# BoostSupply.net
KiCad netlist of a schematic drawn in Altium Designer
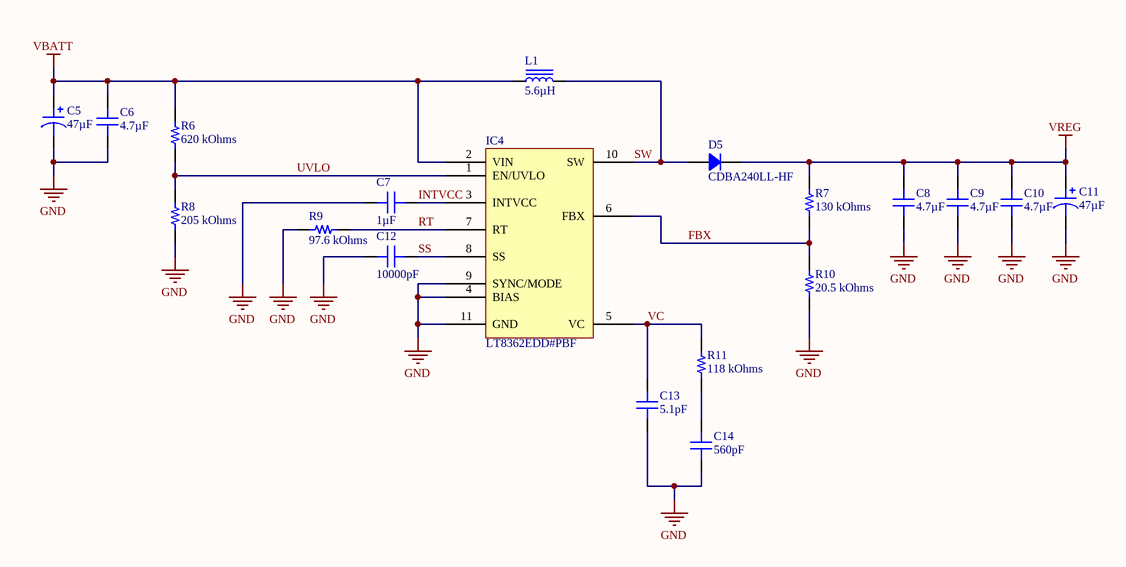
[diagram p0: BoostSupply.SchDoc]

(export (version "E")
  (design (tool "Eeschema 10.0.6"))
  (components
    (comp (ref "C5")
      (value "47µF")
      (footprint "CAP ALSMD 6.6MM H6.1MM")
      (description "ALUMINUM CAPACITOR")
      (fields
        (field (name "PART NUMBER") "HHXD250ARA470MF61G")
        (field (name "MANUFACTURER") "United Chemi-Con")
      )
      (libsource (lib "Celestial Altium Library - altium_library") (part "Polarised Capacitor"))
    )
    (comp (ref "C6")
      (value "4.7µF")
      (footprint "CAP 0805_2012")
      (description "CAP CER 4.7UF 25V X5R 0805")
      (fields (field (name "PART NUMBER") "TMK212ABJ475MG-T") (field (name "MANUFACTURER") "Taiyo Yuden"))
      (libsource (lib "Celestial Altium Library - altium_library") (part "Capacitor"))
    )
    (comp (ref "C7")
      (value "1µF")
      (footprint "CAP 0603_1608")
      (description "CAP CER 1UF 25V X5R 0603")
      (fields (field (name "PART NUMBER") "CC0603KRX5R8BB105") (field (name "MANUFACTURER") "Yageo"))
      (libsource (lib "Celestial Altium Library - altium_library") (part "Capacitor"))
    )
    (comp (ref "C8")
      (value "4.7µF")
      (footprint "CAP 0805_2012")
      (description "CAP CER 4.7UF 25V X5R 0805")
      (fields (field (name "PART NUMBER") "TMK212ABJ475MG-T") (field (name "MANUFACTURER") "Taiyo Yuden"))
      (libsource (lib "Celestial Altium Library - altium_library") (part "Capacitor"))
    )
    (comp (ref "C9")
      (value "4.7µF")
      (footprint "CAP 0805_2012")
      (description "CAP CER 4.7UF 25V X5R 0805")
      (fields (field (name "PART NUMBER") "TMK212ABJ475MG-T") (field (name "MANUFACTURER") "Taiyo Yuden"))
      (libsource (lib "Celestial Altium Library - altium_library") (part "Capacitor"))
    )
    (comp (ref "C10")
      (value "4.7µF")
      (footprint "CAP 0805_2012")
      (description "CAP CER 4.7UF 25V X5R 0805")
      (fields (field (name "PART NUMBER") "TMK212ABJ475MG-T") (field (name "MANUFACTURER") "Taiyo Yuden"))
      (libsource (lib "Celestial Altium Library - altium_library") (part "Capacitor"))
    )
    (comp (ref "C11")
      (value "47µF")
      (footprint "CAP ALSMD 6.6MM H6.1MM")
      (description "ALUMINUM CAPACITOR")
      (fields
        (field (name "PART NUMBER") "HHXD250ARA470MF61G")
        (field (name "MANUFACTURER") "United Chemi-Con")
      )
      (libsource (lib "Celestial Altium Library - altium_library") (part "Polarised Capacitor"))
    )
    (comp (ref "C12")
      (value "10000pF")
      (footprint "CAP 0603_1608")
      (description "CAP CER 10000PF 50V X7R 0603")
      (fields (field (name "PART NUMBER") "AC0603KPX7R9BB103") (field (name "MANUFACTURER") "Yageo"))
      (libsource (lib "Celestial Altium Library - altium_library") (part "Capacitor"))
    )
    (comp (ref "C13")
      (value "5.1pF")
      (footprint "CAP 0603_1608")
      (description "CAP CER 5.1PF 50V C0G/NP0 0603")
      (fields
        (field (name "PART NUMBER") "CL10C5R1CB8NNNC")
        (field (name "MANUFACTURER") "Samsung Electro-Mechanics")
      )
      (libsource (lib "Celestial Altium Library - altium_library") (part "Capacitor"))
    )
    (comp (ref "C14")
      (value "560pF")
      (footprint "CAP 0603_1608")
      (description "CAP CER 560PF 50V C0G/NP0 0603")
      (fields
        (field (name "PART NUMBER") "CL10C561JB8NNNC")
        (field (name "MANUFACTURER") "Samsung Electro-Mechanics")
      )
      (libsource (lib "Celestial Altium Library - altium_library") (part "Capacitor"))
    )
    (comp (ref "D5")
      (value "CDBA240LL-HF")
      (footprint "DO214AC SMA")
      (description "DIODE SCHOTTKY 40V 2A DO214AC")
      (fields (field (name "MANUFACTURER") "Comchip Technology"))
      (libsource (lib "Celestial Altium Library - altium_library") (part "Diode"))
    )
    (comp (ref "IC4")
      (value "LT8362EDD#PBF")
      (footprint "ANALOG DEV DFN-10 3X3MM DD")
      (description "IC REG BST SEPIC 2A 10DFN")
      (fields (field (name "MANUFACTURER") "Linear Technology/Analog Devices"))
      (libsource (lib "Celestial Altium Library - altium_library") (part "ANALOG DEV LT8362 DFN"))
    )
    (comp (ref "L1")
      (value "5.6µH")
      (footprint "TDK SLF12575")
      (description "FIXED IND 5.6UH 6.3A 11.6 MOHM")
      (fields
        (field (name "PART NUMBER") "SLF12575T-5R6N6R3-PF")
        (field (name "MANUFACTURER") "TDK Corporation")
      )
      (libsource (lib "Celestial Altium Library - altium_library") (part "Inductor"))
    )
    (comp (ref "R6")
      (value "620 kOhms")
      (footprint "RES 0603_1608")
      (description "RES SMD 620K OHM 1% 1/10W 0603")
      (fields
        (field (name "PART NUMBER") "ERJ-3EKF6203V")
        (field (name "MANUFACTURER") "Panasonic Electronic Components")
      )
      (libsource (lib "Celestial Altium Library - altium_library") (part "Resistor"))
    )
    (comp (ref "R7")
      (value "130 kOhms")
      (footprint "RES 0603_1608")
      (description "RES SMD 130K OHM 1% 1/10W 0603")
      (fields
        (field (name "PART NUMBER") "ERJ-3EKF1303V")
        (field (name "MANUFACTURER") "Panasonic Electronic Components")
      )
      (libsource (lib "Celestial Altium Library - altium_library") (part "Resistor"))
    )
    (comp (ref "R8")
      (value "205 kOhms")
      (footprint "RES 0603_1608")
      (description "RES SMD 205K OHM 1% 1/10W 0603")
      (fields
        (field (name "PART NUMBER") "ERJ-3EKF2053V")
        (field (name "MANUFACTURER") "Panasonic Electronic Components")
      )
      (libsource (lib "Celestial Altium Library - altium_library") (part "Resistor"))
    )
    (comp (ref "R9")
      (value "97.6 kOhms")
      (footprint "RES 0603_1608")
      (description "RES SMD 97.6K OHM 1% 1/10W 0603")
      (fields
        (field (name "PART NUMBER") "ERJ-3EKF9762V")
        (field (name "MANUFACTURER") "Panasonic Electronic Components")
      )
      (libsource (lib "Celestial Altium Library - altium_library") (part "Resistor"))
    )
    (comp (ref "R10")
      (value "20.5 kOhms")
      (footprint "RES 0603_1608")
      (description "RES SMD 20.5K OHM 1% 1/10W 0603")
      (fields
        (field (name "PART NUMBER") "ERJ-3EKF2052V")
        (field (name "MANUFACTURER") "Panasonic Electronic Components")
      )
      (libsource (lib "Celestial Altium Library - altium_library") (part "Resistor"))
    )
    (comp (ref "R11")
      (value "118 kOhms")
      (footprint "RES 0603_1608")
      (description "RES SMD 118K OHM 1% 1/10W 0603")
      (fields
        (field (name "PART NUMBER") "ERJ-3EKF1183V")
        (field (name "MANUFACTURER") "Panasonic Electronic Components")
      )
      (libsource (lib "Celestial Altium Library - altium_library") (part "Resistor"))
    )
  )
  (nets
    (net (code "1") (name "/FBX") (class "Default")
      (node (ref "IC4") (pin "6") (pinfunction "FBX_6") (pintype "passive"))
      (node (ref "R10") (pin "2") (pinfunction "2_2") (pintype "passive"))
      (node (ref "R7") (pin "1") (pinfunction "1_1") (pintype "passive"))
    )
    (net (code "2") (name "/INTVCC") (class "Default")
      (node (ref "C7") (pin "1") (pinfunction "1_1") (pintype "passive"))
      (node (ref "IC4") (pin "3") (pinfunction "INTVCC_3") (pintype "passive"))
    )
    (net (code "3") (name "/RT") (class "Default")
      (node (ref "IC4") (pin "7") (pinfunction "RT_7") (pintype "passive"))
      (node (ref "R9") (pin "1") (pinfunction "1_1") (pintype "passive"))
    )
    (net (code "4") (name "/SS") (class "Default")
      (node (ref "C12") (pin "1") (pinfunction "1_1") (pintype "passive"))
      (node (ref "IC4") (pin "8") (pinfunction "SS_8") (pintype "passive"))
    )
    (net (code "5") (name "/SW") (class "Default")
      (node (ref "D5") (pin "1") (pinfunction "1_1") (pintype "passive"))
      (node (ref "IC4") (pin "10") (pinfunction "SW_10") (pintype "passive"))
      (node (ref "L1") (pin "2") (pinfunction "2_2") (pintype "passive"))
    )
    (net (code "6") (name "/UVLO") (class "Default")
      (node (ref "IC4") (pin "1") (pinfunction "EN/UVLO_1") (pintype "passive"))
      (node (ref "R6") (pin "1") (pinfunction "1_1") (pintype "passive"))
      (node (ref "R8") (pin "2") (pinfunction "2_2") (pintype "passive"))
    )
    (net (code "7") (name "/VC") (class "Default")
      (node (ref "C13") (pin "2") (pinfunction "2_2") (pintype "passive"))
      (node (ref "IC4") (pin "5") (pinfunction "VC_5") (pintype "passive"))
      (node (ref "R11") (pin "2") (pinfunction "2_2") (pintype "passive"))
    )
    (net (code "8") (name "GND") (class "Default")
      (node (ref "C10") (pin "1") (pinfunction "1_1") (pintype "passive"))
      (node (ref "C11") (pin "2") (pinfunction "2_2") (pintype "passive"))
      (node (ref "C12") (pin "2") (pinfunction "2_2") (pintype "passive"))
      (node (ref "C13") (pin "1") (pinfunction "1_1") (pintype "passive"))
      (node (ref "C14") (pin "1") (pinfunction "1_1") (pintype "passive"))
      (node (ref "C5") (pin "2") (pinfunction "2_2") (pintype "passive"))
      (node (ref "C6") (pin "1") (pinfunction "1_1") (pintype "passive"))
      (node (ref "C7") (pin "2") (pinfunction "2_2") (pintype "passive"))
      (node (ref "C8") (pin "1") (pinfunction "1_1") (pintype "passive"))
      (node (ref "C9") (pin "1") (pinfunction "1_1") (pintype "passive"))
      (node (ref "IC4") (pin "11") (pinfunction "GND_11") (pintype "passive"))
      (node (ref "IC4") (pin "4") (pinfunction "BIAS_4") (pintype "passive"))
      (node (ref "IC4") (pin "9") (pinfunction "SYNC/MODE_9") (pintype "passive"))
      (node (ref "R10") (pin "1") (pinfunction "1_1") (pintype "passive"))
      (node (ref "R8") (pin "1") (pinfunction "1_1") (pintype "passive"))
      (node (ref "R9") (pin "2") (pinfunction "2_2") (pintype "passive"))
    )
    (net (code "9") (name "Net-(C14-Pad2)") (class "Default")
      (node (ref "C14") (pin "2") (pinfunction "2_2") (pintype "passive"))
      (node (ref "R11") (pin "1") (pinfunction "1_1") (pintype "passive"))
    )
    (net (code "10") (name "VBATT") (class "Default")
      (node (ref "C5") (pin "1") (pinfunction "1_1") (pintype "passive"))
      (node (ref "C6") (pin "2") (pinfunction "2_2") (pintype "passive"))
      (node (ref "IC4") (pin "2") (pinfunction "VIN_2") (pintype "passive"))
      (node (ref "L1") (pin "1") (pinfunction "1_1") (pintype "passive"))
      (node (ref "R6") (pin "2") (pinfunction "2_2") (pintype "passive"))
    )
    (net (code "11") (name "VREG") (class "Default")
      (node (ref "C10") (pin "2") (pinfunction "2_2") (pintype "passive"))
      (node (ref "C11") (pin "1") (pinfunction "1_1") (pintype "passive"))
      (node (ref "C8") (pin "2") (pinfunction "2_2") (pintype "passive"))
      (node (ref "C9") (pin "2") (pinfunction "2_2") (pintype "passive"))
      (node (ref "D5") (pin "2") (pinfunction "2_2") (pintype "passive"))
      (node (ref "R7") (pin "2") (pinfunction "2_2") (pintype "passive"))
    )
  )
)
